# esposi-programmer-v1.net
KiCad netlist of a schematic drawn in EAGLE
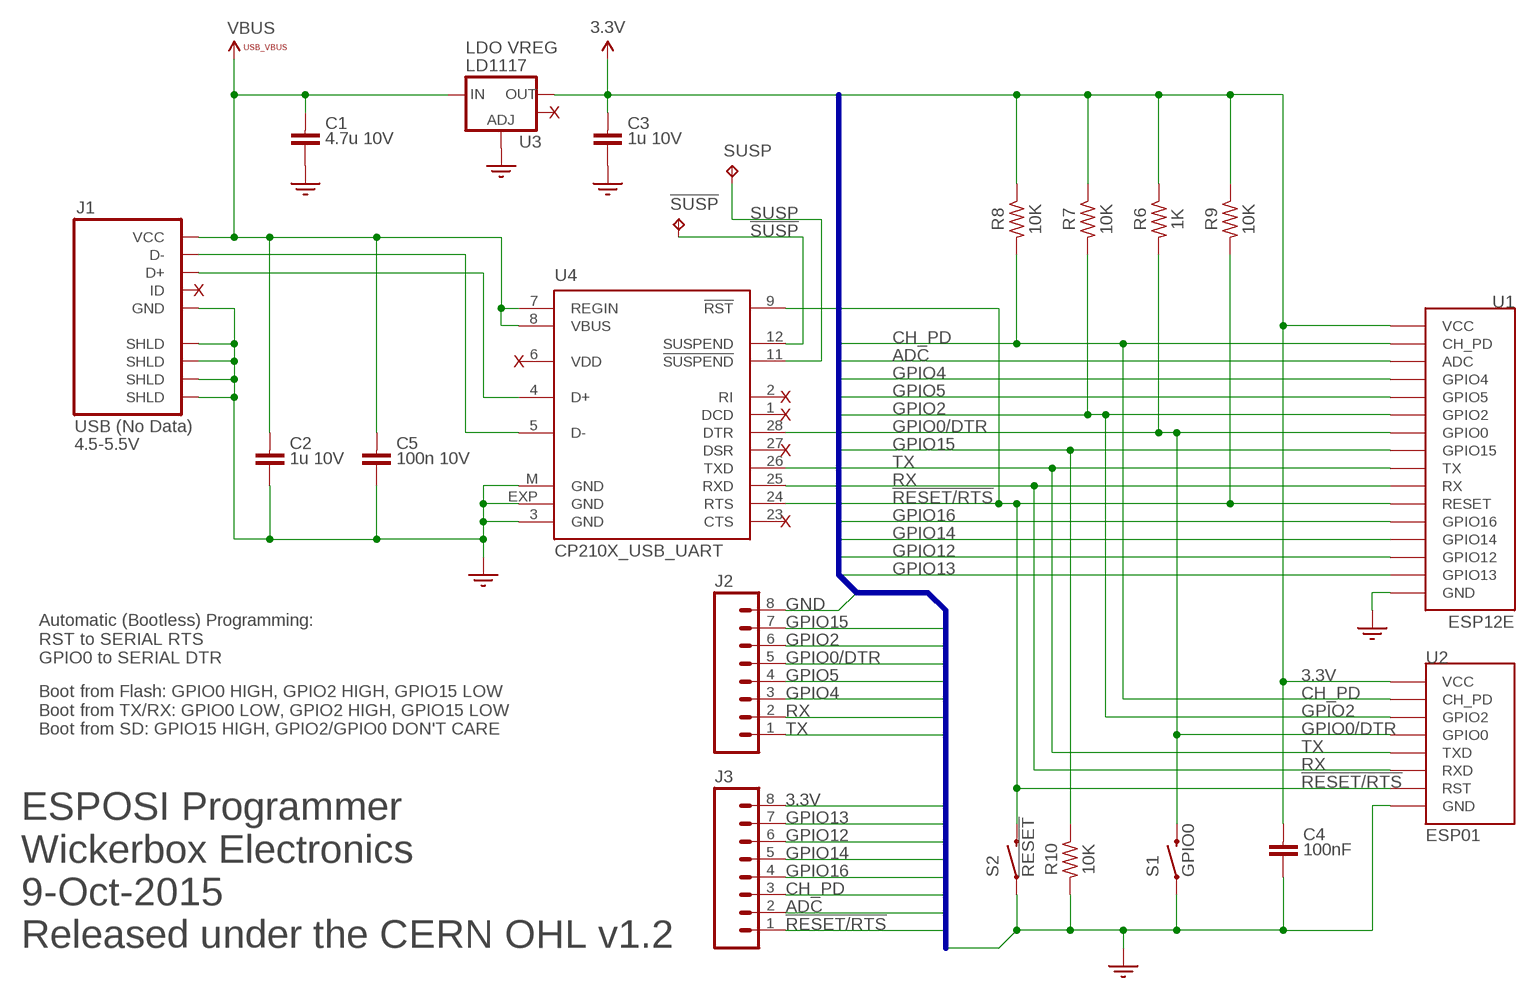
[diagram p0: schematic, sheet 1]

(export (version "E")
  (design (tool "Eeschema 10.0.6"))
  (components
    (comp (ref "!SUSP")
      (value "TESTPAD_TPB1,27")
      (footprint "eagle-import:TESTPAD_B1,27")
      (libsource (lib "eagle-import") (part "TESTPAD_TPB1,27"))
    )
    (comp (ref "C1")
      (value "4.7u 10V")
      (footprint "eagle-import:RLC-0805")
      (libsource (lib "eagle-import") (part "CAP-0805"))
    )
    (comp (ref "C2")
      (value "1u 10V")
      (footprint "eagle-import:RLC-0603")
      (libsource (lib "eagle-import") (part "CAP-0603"))
    )
    (comp (ref "C3")
      (value "1u 10V")
      (footprint "eagle-import:RLC-0603")
      (libsource (lib "eagle-import") (part "CAP-0603"))
    )
    (comp (ref "C4")
      (value "100nF")
      (footprint "eagle-import:RLC-0402")
      (libsource (lib "eagle-import") (part "CAP-0402"))
    )
    (comp (ref "C5")
      (value "100n 10V")
      (footprint "eagle-import:RLC-0402")
      (libsource (lib "eagle-import") (part "CAP-0402"))
    )
    (comp (ref "J1")
      (value "USB (No Data)")
      (footprint "eagle-import:ZX62D-B-5P8")
      (libsource (lib "eagle-import") (part "ZX62D-B-5P8"))
    )
    (comp (ref "J2")
      (value "M08NO_SILK_FEMALE_PTH")
      (footprint "eagle-import:1X08_NO_SILK")
      (libsource (lib "eagle-import") (part "M08NO_SILK_FEMALE_PTH"))
    )
    (comp (ref "J3")
      (value "M08NO_SILK_FEMALE_PTH")
      (footprint "eagle-import:1X08_NO_SILK")
      (libsource (lib "eagle-import") (part "M08NO_SILK_FEMALE_PTH"))
    )
    (comp (ref "R6")
      (value "1K")
      (footprint "eagle-import:RLC-0402")
      (libsource (lib "eagle-import") (part "RES-0402"))
    )
    (comp (ref "R7")
      (value "10K")
      (footprint "eagle-import:RLC-0402")
      (libsource (lib "eagle-import") (part "RES-0402"))
    )
    (comp (ref "R8")
      (value "10K")
      (footprint "eagle-import:RLC-0402")
      (libsource (lib "eagle-import") (part "RES-0402"))
    )
    (comp (ref "R9")
      (value "10K")
      (footprint "eagle-import:RLC-0402")
      (libsource (lib "eagle-import") (part "RES-0402"))
    )
    (comp (ref "R10")
      (value "10K")
      (footprint "eagle-import:RLC-0402")
      (libsource (lib "eagle-import") (part "RES-0402"))
    )
    (comp (ref "S1")
      (value "GPIO0")
      (footprint "eagle-import:TACTILE-SWITCH-1101NE")
      (libsource (lib "eagle-import") (part "SWITCH-MOMENTARY-2SMD-1101NE"))
    )
    (comp (ref "S2")
      (value "!RESET")
      (footprint "eagle-import:TACTILE-SWITCH-1101NE")
      (libsource (lib "eagle-import") (part "SWITCH-MOMENTARY-2SMD-1101NE"))
    )
    (comp (ref "SUSP")
      (value "TESTPAD_TPB1,27")
      (footprint "eagle-import:TESTPAD_B1,27")
      (libsource (lib "eagle-import") (part "TESTPAD_TPB1,27"))
    )
    (comp (ref "U1")
      (value "ESP12E")
      (footprint "eagle-import:ESP12")
      (libsource (lib "eagle-import") (part "ESP12-LONGTH"))
    )
    (comp (ref "U2")
      (value "ESP01")
      (footprint "eagle-import:ESP01")
      (libsource (lib "eagle-import") (part "ESP01-LONG"))
    )
    (comp (ref "U3")
      (value "V_REG_LM1117SOT223")
      (footprint "eagle-import:SOT223")
      (libsource (lib "eagle-import") (part "V_REG_LM1117SOT223"))
    )
    (comp (ref "U4")
      (value "CP210X_USB_UART")
      (footprint "eagle-import:MLP28")
      (libsource (lib "eagle-import") (part "CP210X_USB_UART"))
    )
  )
  (nets
    (net (code "1") (name "/ADC") (class "Default")
      (node (ref "J3") (pin "2") (pinfunction "2_2") (pintype "passive"))
      (node (ref "U1") (pin "ADC") (pinfunction "ADC_ADC") (pintype "bidirectional"))
    )
    (net (code "2") (name "/CH_PD") (class "Default")
      (node (ref "J3") (pin "3") (pinfunction "3_3") (pintype "passive"))
      (node (ref "R8") (pin "2") (pinfunction "2_2") (pintype "passive"))
      (node (ref "U1") (pin "CH_PD") (pinfunction "CH_PD_CH_PD") (pintype "bidirectional"))
      (node (ref "U2") (pin "CH_PD") (pinfunction "CH_PD_CH_PD") (pintype "bidirectional"))
    )
    (net (code "3") (name "/GPIO0{slash}DTR") (class "Default")
      (node (ref "J2") (pin "5") (pinfunction "5_5") (pintype "passive"))
      (node (ref "R6") (pin "2") (pinfunction "2_2") (pintype "passive"))
      (node (ref "S1") (pin "2") (pinfunction "2_2") (pintype "passive"))
      (node (ref "U1") (pin "GPIO0") (pinfunction "GPIO0_GPIO0") (pintype "bidirectional"))
      (node (ref "U2") (pin "GPIO0") (pinfunction "GPIO0_GPIO0") (pintype "bidirectional"))
      (node (ref "U4") (pin "28") (pinfunction "DTR_28") (pintype "output"))
    )
    (net (code "4") (name "/GPIO2") (class "Default")
      (node (ref "J2") (pin "6") (pinfunction "6_6") (pintype "passive"))
      (node (ref "R7") (pin "2") (pinfunction "2_2") (pintype "passive"))
      (node (ref "U1") (pin "GPIO2") (pinfunction "GPIO2_GPIO2") (pintype "bidirectional"))
      (node (ref "U2") (pin "GPIO2") (pinfunction "GPIO2_GPIO2") (pintype "bidirectional"))
    )
    (net (code "5") (name "/GPIO4") (class "Default")
      (node (ref "J2") (pin "3") (pinfunction "3_3") (pintype "passive"))
      (node (ref "U1") (pin "GPIO4") (pinfunction "GPIO4_GPIO4") (pintype "bidirectional"))
    )
    (net (code "6") (name "/GPIO5") (class "Default")
      (node (ref "J2") (pin "4") (pinfunction "4_4") (pintype "passive"))
      (node (ref "U1") (pin "GPIO5") (pinfunction "GPIO5_GPIO5") (pintype "bidirectional"))
    )
    (net (code "7") (name "/GPIO12") (class "Default")
      (node (ref "J3") (pin "6") (pinfunction "6_6") (pintype "passive"))
      (node (ref "U1") (pin "GPIO12") (pinfunction "GPIO12_GPIO12") (pintype "bidirectional"))
    )
    (net (code "8") (name "/GPIO13") (class "Default")
      (node (ref "J3") (pin "7") (pinfunction "7_7") (pintype "passive"))
      (node (ref "U1") (pin "GPIO13") (pinfunction "GPIO13_GPIO13") (pintype "bidirectional"))
    )
    (net (code "9") (name "/GPIO14") (class "Default")
      (node (ref "J3") (pin "5") (pinfunction "5_5") (pintype "passive"))
      (node (ref "U1") (pin "GPIO14") (pinfunction "GPIO14_GPIO14") (pintype "bidirectional"))
    )
    (net (code "10") (name "/GPIO15") (class "Default")
      (node (ref "J2") (pin "7") (pinfunction "7_7") (pintype "passive"))
      (node (ref "R10") (pin "1") (pinfunction "1_1") (pintype "passive"))
      (node (ref "U1") (pin "GPIO15") (pinfunction "GPIO15_GPIO15") (pintype "bidirectional"))
    )
    (net (code "11") (name "/GPIO16") (class "Default")
      (node (ref "J3") (pin "4") (pinfunction "4_4") (pintype "passive"))
      (node (ref "U1") (pin "GPIO16") (pinfunction "GPIO16_GPIO16") (pintype "bidirectional"))
    )
    (net (code "12") (name "/RX") (class "Default")
      (node (ref "J2") (pin "2") (pinfunction "2_2") (pintype "passive"))
      (node (ref "U1") (pin "RX") (pinfunction "RX_RX") (pintype "bidirectional"))
      (node (ref "U2") (pin "RX") (pinfunction "RXD_RX") (pintype "bidirectional"))
      (node (ref "U4") (pin "25") (pinfunction "RXD_25") (pintype "input"))
    )
    (net (code "13") (name "/SUSP") (class "Default")
      (node (ref "SUSP") (pin "TP") (pinfunction "TP_TP") (pintype "input"))
      (node (ref "U4") (pin "11") (pinfunction "~{SUSPEND}_11") (pintype "output"))
    )
    (net (code "14") (name "/TX") (class "Default")
      (node (ref "J2") (pin "1") (pinfunction "1_1") (pintype "passive"))
      (node (ref "U1") (pin "TX") (pinfunction "TX_TX") (pintype "bidirectional"))
      (node (ref "U2") (pin "TX") (pinfunction "TXD_TX") (pintype "bidirectional"))
      (node (ref "U4") (pin "26") (pinfunction "TXD_26") (pintype "output"))
    )
    (net (code "15") (name "/VDD") (class "Default")
      (node (ref "U4") (pin "6") (pinfunction "VDD_6") (pintype "power_in"))
    )
    (net (code "16") (name "/~{RESET{slash}RTS}") (class "Default")
      (node (ref "J3") (pin "1") (pinfunction "1_1") (pintype "passive"))
      (node (ref "R9") (pin "2") (pinfunction "2_2") (pintype "passive"))
      (node (ref "S2") (pin "2") (pinfunction "2_2") (pintype "passive"))
      (node (ref "U1") (pin "RESET") (pinfunction "RESET_RESET") (pintype "bidirectional"))
      (node (ref "U2") (pin "RST") (pinfunction "RST_RST") (pintype "bidirectional"))
      (node (ref "U4") (pin "24") (pinfunction "RTS_24") (pintype "output"))
      (node (ref "U4") (pin "9") (pinfunction "~{RST}_9") (pintype "bidirectional"))
    )
    (net (code "17") (name "/~{SUSP}") (class "Default")
      (node (ref "!SUSP") (pin "TP") (pinfunction "TP_TP") (pintype "input"))
      (node (ref "U4") (pin "12") (pinfunction "SUSPEND_12") (pintype "output"))
    )
    (net (code "18") (name "3.3V") (class "Default")
      (node (ref "C3") (pin "2") (pinfunction "1_2") (pintype "passive"))
      (node (ref "C4") (pin "1") (pinfunction "1_1") (pintype "passive"))
      (node (ref "J3") (pin "8") (pinfunction "8_8") (pintype "passive"))
      (node (ref "R6") (pin "1") (pinfunction "1_1") (pintype "passive"))
      (node (ref "R7") (pin "1") (pinfunction "1_1") (pintype "passive"))
      (node (ref "R8") (pin "1") (pinfunction "1_1") (pintype "passive"))
      (node (ref "R9") (pin "1") (pinfunction "1_1") (pintype "passive"))
      (node (ref "U1") (pin "VCC") (pinfunction "VCC_VCC") (pintype "bidirectional"))
      (node (ref "U2") (pin "VCC") (pinfunction "VCC_VCC") (pintype "bidirectional"))
      (node (ref "U3") (pin "2") (pinfunction "OUT_2") (pintype "output"))
    )
    (net (code "19") (name "GND") (class "Default")
      (node (ref "C1") (pin "2") (pinfunction "2_2") (pintype "passive"))
      (node (ref "C2") (pin "1") (pinfunction "2_1") (pintype "passive"))
      (node (ref "C3") (pin "1") (pinfunction "2_1") (pintype "passive"))
      (node (ref "C4") (pin "2") (pinfunction "2_2") (pintype "passive"))
      (node (ref "C5") (pin "2") (pinfunction "2_2") (pintype "passive"))
      (node (ref "J1") (pin "P$1") (pinfunction "SHLD_P$1") (pintype "power_in"))
      (node (ref "J1") (pin "P$2") (pinfunction "SHLD_P$2") (pintype "power_in"))
      (node (ref "J1") (pin "P$3") (pinfunction "SHLD_P$3") (pintype "power_in"))
      (node (ref "J1") (pin "P$4") (pinfunction "SHLD_P$4") (pintype "power_in"))
      (node (ref "J1") (pin "P5") (pinfunction "GND_P5") (pintype "power_in"))
      (node (ref "J2") (pin "8") (pinfunction "8_8") (pintype "passive"))
      (node (ref "R10") (pin "2") (pinfunction "2_2") (pintype "passive"))
      (node (ref "S1") (pin "1") (pinfunction "1_1") (pintype "passive"))
      (node (ref "S2") (pin "1") (pinfunction "1_1") (pintype "passive"))
      (node (ref "U1") (pin "GND") (pinfunction "GND_GND") (pintype "bidirectional"))
      (node (ref "U2") (pin "GND") (pinfunction "GND_GND") (pintype "bidirectional"))
      (node (ref "U3") (pin "1") (pinfunction "ADJ_1") (pintype "input"))
      (node (ref "U4") (pin "3") (pinfunction "GND_3") (pintype "power_in"))
      (node (ref "U4") (pin "EXP") (pinfunction "GND_EXP") (pintype "power_in"))
      (node (ref "U4") (pin "M") (pinfunction "GND_M") (pintype "power_in"))
    )
    (net (code "20") (name "Net-(J1-D+)") (class "Default")
      (node (ref "J1") (pin "P3") (pinfunction "D+_P3") (pintype "bidirectional"))
      (node (ref "U4") (pin "4") (pinfunction "D+_4") (pintype "bidirectional"))
    )
    (net (code "21") (name "Net-(J1-D-)") (class "Default")
      (node (ref "J1") (pin "P2") (pinfunction "D-_P2") (pintype "bidirectional"))
      (node (ref "U4") (pin "5") (pinfunction "D-_5") (pintype "bidirectional"))
    )
    (net (code "22") (name "VBUS") (class "Default")
      (node (ref "C1") (pin "1") (pinfunction "1_1") (pintype "passive"))
      (node (ref "C2") (pin "2") (pinfunction "1_2") (pintype "passive"))
      (node (ref "C5") (pin "1") (pinfunction "1_1") (pintype "passive"))
      (node (ref "J1") (pin "P1") (pinfunction "VCC_P1") (pintype "power_in"))
      (node (ref "U3") (pin "3") (pinfunction "IN_3") (pintype "input"))
      (node (ref "U4") (pin "7") (pinfunction "REGIN_7") (pintype "passive"))
      (node (ref "U4") (pin "8") (pinfunction "VBUS_8") (pintype "input"))
    )
    (net (code "23") (name "unconnected-(J1-ID-PadP4)") (class "Default")
      (node (ref "J1") (pin "P4") (pinfunction "ID_P4") (pintype "bidirectional"))
    )
    (net (code "24") (name "unconnected-(U3-OUT-Pad4)") (class "Default")
      (node (ref "U3") (pin "4") (pinfunction "OUT_4") (pintype "output"))
    )
    (net (code "25") (name "unconnected-(U4-CTS-Pad23)") (class "Default")
      (node (ref "U4") (pin "23") (pinfunction "CTS_23") (pintype "input"))
    )
    (net (code "26") (name "unconnected-(U4-DCD-Pad1)") (class "Default")
      (node (ref "U4") (pin "1") (pinfunction "DCD_1") (pintype "input"))
    )
    (net (code "27") (name "unconnected-(U4-DSR-Pad27)") (class "Default")
      (node (ref "U4") (pin "27") (pinfunction "DSR_27") (pintype "input"))
    )
    (net (code "28") (name "unconnected-(U4-RI-Pad2)") (class "Default")
      (node (ref "U4") (pin "2") (pinfunction "RI_2") (pintype "input"))
    )
  )
)
